# sensor_breakout.net
KiCad netlist of a schematic drawn in EAGLE
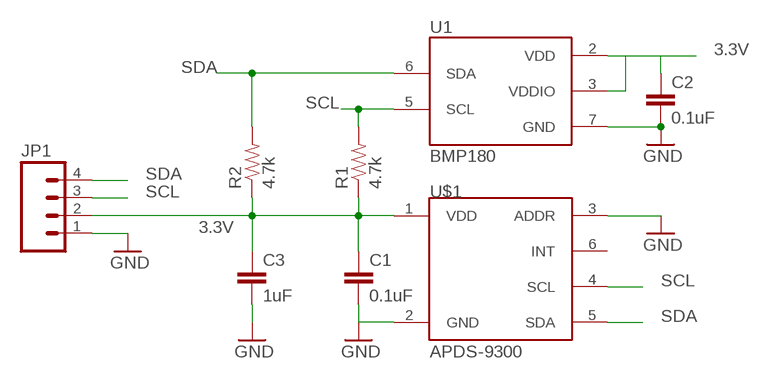
[diagram p0: schematic, sheet 1]

(export (version "E")
  (design (tool "Eeschema 10.0.6"))
  (components
    (comp (ref "C1")
      (value "0.1uF")
      (footprint "eagle-import:0402-S")
      (libsource (lib "eagle-import") (part "CAP0402-S"))
    )
    (comp (ref "C2")
      (value "0.1uF")
      (footprint "eagle-import:0402-S")
      (libsource (lib "eagle-import") (part "CAP0402-S"))
    )
    (comp (ref "C3")
      (value "1uF")
      (footprint "eagle-import:0402-S")
      (libsource (lib "eagle-import") (part "CAP0402-S"))
    )
    (comp (ref "JP1")
      (value "M04LOCK")
      (footprint "eagle-import:1X04_LOCK")
      (libsource (lib "eagle-import") (part "M04LOCK"))
    )
    (comp (ref "R1")
      (value "4.7k")
      (footprint "eagle-import:0402-S")
      (libsource (lib "eagle-import") (part "RESISTOR0402-S"))
    )
    (comp (ref "R2")
      (value "4.7k")
      (footprint "eagle-import:0402-S")
      (libsource (lib "eagle-import") (part "RESISTOR0402-S"))
    )
    (comp (ref "U$1")
      (value "APDS-9300")
      (footprint "eagle-import:CHIPLED")
      (libsource (lib "eagle-import") (part "APDS-9300"))
    )
    (comp (ref "U1")
      (value "BMP180")
      (footprint "eagle-import:BMP180")
      (libsource (lib "eagle-import") (part "BMP180"))
    )
  )
  (nets
    (net (code "1") (name "/3.3V") (class "Default")
      (node (ref "C1") (pin "1") (pinfunction "1_1") (pintype "passive"))
      (node (ref "C2") (pin "1") (pinfunction "1_1") (pintype "passive"))
      (node (ref "C3") (pin "1") (pinfunction "1_1") (pintype "passive"))
      (node (ref "JP1") (pin "2") (pinfunction "2_2") (pintype "passive"))
      (node (ref "R1") (pin "1") (pinfunction "1_1") (pintype "passive"))
      (node (ref "R2") (pin "1") (pinfunction "1_1") (pintype "passive"))
      (node (ref "U$1") (pin "1") (pinfunction "VDD_1") (pintype "bidirectional"))
      (node (ref "U1") (pin "2") (pinfunction "VDD_2") (pintype "power_in"))
      (node (ref "U1") (pin "3") (pinfunction "VDDIO_3") (pintype "power_in"))
    )
    (net (code "2") (name "/SCL") (class "Default")
      (node (ref "JP1") (pin "3") (pinfunction "3_3") (pintype "passive"))
      (node (ref "R1") (pin "2") (pinfunction "2_2") (pintype "passive"))
      (node (ref "U$1") (pin "4") (pinfunction "SCL_4") (pintype "bidirectional"))
      (node (ref "U1") (pin "5") (pinfunction "SCL_5") (pintype "input"))
    )
    (net (code "3") (name "/SDA") (class "Default")
      (node (ref "JP1") (pin "4") (pinfunction "4_4") (pintype "passive"))
      (node (ref "R2") (pin "2") (pinfunction "2_2") (pintype "passive"))
      (node (ref "U$1") (pin "5") (pinfunction "SDA_5") (pintype "bidirectional"))
      (node (ref "U1") (pin "6") (pinfunction "SDA_6") (pintype "bidirectional"))
    )
    (net (code "4") (name "GND") (class "Default")
      (node (ref "C1") (pin "2") (pinfunction "2_2") (pintype "passive"))
      (node (ref "C2") (pin "2") (pinfunction "2_2") (pintype "passive"))
      (node (ref "C3") (pin "2") (pinfunction "2_2") (pintype "passive"))
      (node (ref "JP1") (pin "1") (pinfunction "1_1") (pintype "passive"))
      (node (ref "U$1") (pin "2") (pinfunction "GND_2") (pintype "bidirectional"))
      (node (ref "U$1") (pin "3") (pinfunction "ADDR_3") (pintype "bidirectional"))
      (node (ref "U1") (pin "7") (pinfunction "GND_7") (pintype "power_in"))
    )
    (net (code "5") (name "unconnected-(U$1-INT-Pad6)") (class "Default")
      (node (ref "U$1") (pin "6") (pinfunction "INT_6") (pintype "bidirectional"))
    )
  )
)
